# MAX_SEG.net
KiCad netlist of a schematic drawn in Altium Designer
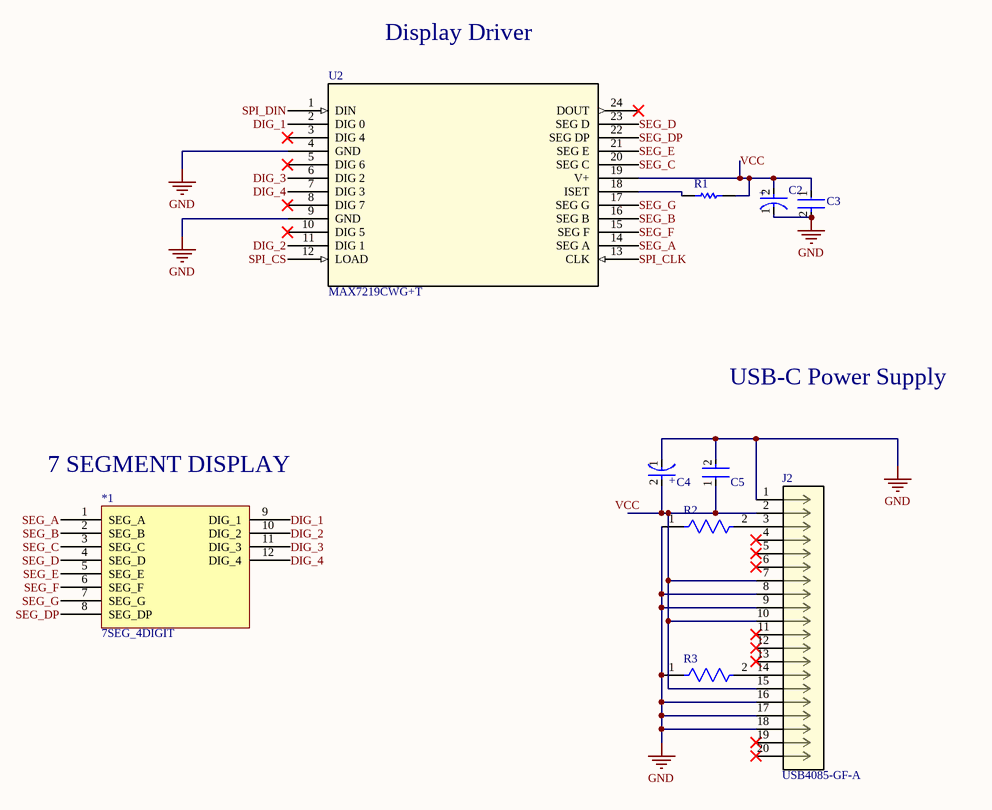
[diagram p0: MAX_SEG.SchDoc]

(export (version "E")
  (design (tool "Eeschema 10.0.6"))
  (components
    (comp (ref "*1")
      (value "7SEG_4DIGIT")
      (footprint "PCBComponent_1")
      (description "4 Digit 7 Segment Common Cathode Display")
      (libsource (lib "7SEF_4DIGIT") (part "7SEG_4DIGIT"))
    )
    (comp (ref "C2")
      (value "TAJB106K010RNJ")
      (footprint "FP-TAJB-MFG")
      (description "10uF 10V  ±10% 2.1Ω 1210  SMD Tantalum Capacitor")
      (fields (field (name "TOLERANCE") "10%") (field (name "VOLTAGE") "10V"))
      (libsource (lib "Altium Content Vault") (part "203bc49f2ac43e59fd269a8c329ed05"))
    )
    (comp (ref "C3")
      (value "GRM155R71C104KA88D")
      (footprint "FP-GRM15-MFG")
      (description "CAP CER 0.1UF 16V X7R 0402")
      (fields
        (field (name "TOLERANCE") "10%")
        (field (name "OCTOPART") "https://octopart.com/grm155r71c104ka88d-murata-196880")
      )
      (libsource (lib "Altium Content Vault") (part "236180d848d6139a670b325ea6854c9"))
    )
    (comp (ref "C4")
      (value "TAJB106K010RNJ")
      (footprint "FP-TAJB-MFG")
      (description "10uF 10V  ±10% 2.1Ω 1210  SMD Tantalum Capacitor")
      (fields (field (name "TOLERANCE") "10%") (field (name "VOLTAGE") "10V"))
      (libsource (lib "Altium Content Vault") (part "203bc49f2ac43e59fd269a8c329ed05"))
    )
    (comp (ref "C5")
      (value "GRM155R71C104KA88D")
      (footprint "FP-GRM15-MFG")
      (description "CAP CER 0.1UF 16V X7R 0402")
      (fields
        (field (name "TOLERANCE") "10%")
        (field (name "OCTOPART") "https://octopart.com/grm155r71c104ka88d-murata-196880")
      )
      (libsource (lib "Altium Content Vault") (part "236180d848d6139a670b325ea6854c9"))
    )
    (comp (ref "J2")
      (value "USB4085-GF-A")
      (footprint "CONN16_USB4085-GF-A_GCT")
      (description "Description")
      (fields (field (name "COPYRIGHT") "Copyright (C) 2025 Ultra Librarian. All rights reserved."))
      (libsource (lib "USB4085-GF-A") (part "USB4085-GF-A"))
    )
    (comp (ref "R1")
      (value "RC0402FR-0710KL")
      (footprint "RESC1005X40X25LL05T10")
      (fields (field (name "MANUFACTURER") "Yageo / Phycomp"))
      (libsource (lib "Altium Content Vault") (part "RES"))
    )
    (comp (ref "R2")
      (value "RN73R1ETTP5101F25")
      (footprint "FP-RN73R1E-IPC_C")
      (description "5.1kΩ ±1% 0.063W, 1/16W Chip Resistor 0402 (1005 Metric) Moisture Resistant Thin Film")
      (libsource (lib "Altium Content Vault") (part "1029c3af85768c4190bb7ad29bc67b5"))
    )
    (comp (ref "R3")
      (value "RN73R1ETTP5101F25")
      (footprint "FP-RN73R1E-IPC_C")
      (description "5.1kΩ ±1% 0.063W, 1/16W Chip Resistor 0402 (1005 Metric) Moisture Resistant Thin Film")
      (libsource (lib "Altium Content Vault") (part "1029c3af85768c4190bb7ad29bc67b5"))
    )
    (comp (ref "U2")
      (value "MAX7219CWG+T")
      (footprint "21-0042B_24_MXM")
      (description "Serially Interfaced, 8-Digit, LED Display Drivers")
      (fields (field (name "COPYRIGHT") "Copyright (C) 2026 Ultra Librarian. All rights reserved."))
      (libsource (lib "MAX7219CWG&plus_T") (part "MAX7219CWG+T"))
    )
  )
  (nets
    (net (code "1") (name "/DIG_1") (class "Default")
      (node (ref "*1") (pin "9") (pinfunction "DIG_1_9") (pintype "passive"))
      (node (ref "U2") (pin "2") (pinfunction "DIG_0_2") (pintype "passive"))
    )
    (net (code "2") (name "/DIG_2") (class "Default")
      (node (ref "*1") (pin "10") (pinfunction "DIG_2_10") (pintype "passive"))
      (node (ref "U2") (pin "11") (pinfunction "DIG_1_11") (pintype "passive"))
    )
    (net (code "3") (name "/DIG_3") (class "Default")
      (node (ref "*1") (pin "11") (pinfunction "DIG_3_11") (pintype "passive"))
      (node (ref "U2") (pin "6") (pinfunction "DIG_2_6") (pintype "passive"))
    )
    (net (code "4") (name "/DIG_4") (class "Default")
      (node (ref "*1") (pin "12") (pinfunction "DIG_4_12") (pintype "passive"))
      (node (ref "U2") (pin "7") (pinfunction "DIG_3_7") (pintype "passive"))
    )
    (net (code "5") (name "/SEG_A") (class "Default")
      (node (ref "*1") (pin "1") (pinfunction "SEG_A_1") (pintype "passive"))
      (node (ref "U2") (pin "14") (pinfunction "SEG_A_14") (pintype "passive"))
    )
    (net (code "6") (name "/SEG_B") (class "Default")
      (node (ref "*1") (pin "2") (pinfunction "SEG_B_2") (pintype "passive"))
      (node (ref "U2") (pin "16") (pinfunction "SEG_B_16") (pintype "passive"))
    )
    (net (code "7") (name "/SEG_C") (class "Default")
      (node (ref "*1") (pin "3") (pinfunction "SEG_C_3") (pintype "passive"))
      (node (ref "U2") (pin "20") (pinfunction "SEG_C_20") (pintype "passive"))
    )
    (net (code "8") (name "/SEG_D") (class "Default")
      (node (ref "*1") (pin "4") (pinfunction "SEG_D_4") (pintype "passive"))
      (node (ref "U2") (pin "23") (pinfunction "SEG_D_23") (pintype "passive"))
    )
    (net (code "9") (name "/SEG_DP") (class "Default")
      (node (ref "*1") (pin "8") (pinfunction "SEG_DP_8") (pintype "passive"))
      (node (ref "U2") (pin "22") (pinfunction "SEG_DP_22") (pintype "passive"))
    )
    (net (code "10") (name "/SEG_E") (class "Default")
      (node (ref "*1") (pin "5") (pinfunction "SEG_E_5") (pintype "passive"))
      (node (ref "U2") (pin "21") (pinfunction "SEG_E_21") (pintype "passive"))
    )
    (net (code "11") (name "/SEG_F") (class "Default")
      (node (ref "*1") (pin "6") (pinfunction "SEG_F_6") (pintype "passive"))
      (node (ref "U2") (pin "15") (pinfunction "SEG_F_15") (pintype "passive"))
    )
    (net (code "12") (name "/SEG_G") (class "Default")
      (node (ref "*1") (pin "7") (pinfunction "SEG_G_7") (pintype "passive"))
      (node (ref "U2") (pin "17") (pinfunction "SEG_G_17") (pintype "passive"))
    )
    (net (code "13") (name "/SPI_CLK") (class "Default")
      (node (ref "U2") (pin "13") (pinfunction "CLK_13") (pintype "input"))
    )
    (net (code "14") (name "/SPI_CS") (class "Default")
      (node (ref "U2") (pin "12") (pinfunction "LOAD_12") (pintype "input"))
    )
    (net (code "15") (name "/SPI_DIN") (class "Default")
      (node (ref "U2") (pin "1") (pinfunction "DIN_1") (pintype "input"))
    )
    (net (code "16") (name "/VCC") (class "Default")
      (node (ref "C2") (pin "2") (pinfunction "A_2") (pintype "passive"))
      (node (ref "C3") (pin "1") (pinfunction "1_1") (pintype "passive"))
      (node (ref "C4") (pin "2") (pinfunction "A_2") (pintype "passive"))
      (node (ref "C5") (pin "1") (pinfunction "1_1") (pintype "passive"))
      (node (ref "J2") (pin "10") (pinfunction "10_10") (pintype "passive"))
      (node (ref "J2") (pin "15") (pinfunction "15_15") (pintype "passive"))
      (node (ref "J2") (pin "2") (pinfunction "2_2") (pintype "passive"))
      (node (ref "J2") (pin "7") (pinfunction "7_7") (pintype "passive"))
      (node (ref "R1") (pin "2") (pinfunction "2_2") (pintype "passive"))
      (node (ref "U2") (pin "19") (pinfunction "V+_19") (pintype "power_in"))
    )
    (net (code "17") (name "GND") (class "Default")
      (node (ref "C2") (pin "1") (pinfunction "C_1") (pintype "passive"))
      (node (ref "C3") (pin "2") (pinfunction "2_2") (pintype "passive"))
      (node (ref "C4") (pin "1") (pinfunction "C_1") (pintype "passive"))
      (node (ref "C5") (pin "2") (pinfunction "2_2") (pintype "passive"))
      (node (ref "J2") (pin "1") (pinfunction "1_1") (pintype "passive"))
      (node (ref "J2") (pin "16") (pinfunction "16_16") (pintype "passive"))
      (node (ref "J2") (pin "17") (pinfunction "17_17") (pintype "passive"))
      (node (ref "J2") (pin "18") (pinfunction "18_18") (pintype "passive"))
      (node (ref "J2") (pin "8") (pinfunction "8_8") (pintype "passive"))
      (node (ref "J2") (pin "9") (pinfunction "9_9") (pintype "passive"))
      (node (ref "R2") (pin "1") (pinfunction "1_1") (pintype "passive"))
      (node (ref "R3") (pin "1") (pinfunction "1_1") (pintype "passive"))
      (node (ref "U2") (pin "4") (pinfunction "GND_4") (pintype "power_in"))
      (node (ref "U2") (pin "9") (pinfunction "GND_9") (pintype "power_in"))
    )
    (net (code "18") (name "Net-(J2-Pad3)") (class "Default")
      (node (ref "J2") (pin "3") (pinfunction "3_3") (pintype "passive"))
      (node (ref "R2") (pin "2") (pinfunction "2_2") (pintype "passive"))
    )
    (net (code "19") (name "Net-(J2-Pad14)") (class "Default")
      (node (ref "J2") (pin "14") (pinfunction "14_14") (pintype "passive"))
      (node (ref "R3") (pin "2") (pinfunction "2_2") (pintype "passive"))
    )
    (net (code "20") (name "Net-(U2-ISET)") (class "Default")
      (node (ref "R1") (pin "1") (pinfunction "1_1") (pintype "passive"))
      (node (ref "U2") (pin "18") (pinfunction "ISET_18") (pintype "passive"))
    )
    (net (code "21") (name "unconnected-(J2-Pad4)") (class "Default")
      (node (ref "J2") (pin "4") (pinfunction "4_4") (pintype "passive+no_connect"))
    )
    (net (code "22") (name "unconnected-(J2-Pad5)") (class "Default")
      (node (ref "J2") (pin "5") (pinfunction "5_5") (pintype "passive+no_connect"))
    )
    (net (code "23") (name "unconnected-(J2-Pad6)") (class "Default")
      (node (ref "J2") (pin "6") (pinfunction "6_6") (pintype "passive+no_connect"))
    )
    (net (code "24") (name "unconnected-(J2-Pad11)") (class "Default")
      (node (ref "J2") (pin "11") (pinfunction "11_11") (pintype "passive+no_connect"))
    )
    (net (code "25") (name "unconnected-(J2-Pad12)") (class "Default")
      (node (ref "J2") (pin "12") (pinfunction "12_12") (pintype "passive+no_connect"))
    )
    (net (code "26") (name "unconnected-(J2-Pad13)") (class "Default")
      (node (ref "J2") (pin "13") (pinfunction "13_13") (pintype "passive+no_connect"))
    )
    (net (code "27") (name "unconnected-(J2-Pad19)") (class "Default")
      (node (ref "J2") (pin "19") (pinfunction "19_19") (pintype "passive+no_connect"))
    )
    (net (code "28") (name "unconnected-(J2-Pad20)") (class "Default")
      (node (ref "J2") (pin "20") (pinfunction "20_20") (pintype "passive+no_connect"))
    )
    (net (code "29") (name "unconnected-(U2-DIG_4-Pad3)") (class "Default")
      (node (ref "U2") (pin "3") (pinfunction "DIG_4_3") (pintype "passive+no_connect"))
    )
    (net (code "30") (name "unconnected-(U2-DIG_5-Pad10)") (class "Default")
      (node (ref "U2") (pin "10") (pinfunction "DIG_5_10") (pintype "passive+no_connect"))
    )
    (net (code "31") (name "unconnected-(U2-DIG_6-Pad5)") (class "Default")
      (node (ref "U2") (pin "5") (pinfunction "DIG_6_5") (pintype "passive+no_connect"))
    )
    (net (code "32") (name "unconnected-(U2-DIG_7-Pad8)") (class "Default")
      (node (ref "U2") (pin "8") (pinfunction "DIG_7_8") (pintype "passive+no_connect"))
    )
    (net (code "33") (name "unconnected-(U2-DOUT-Pad24)") (class "Default")
      (node (ref "U2") (pin "24") (pinfunction "DOUT_24") (pintype "output+no_connect"))
    )
  )
)
